# dac-layout.net
KiCad netlist of a schematic drawn in Altium Designer
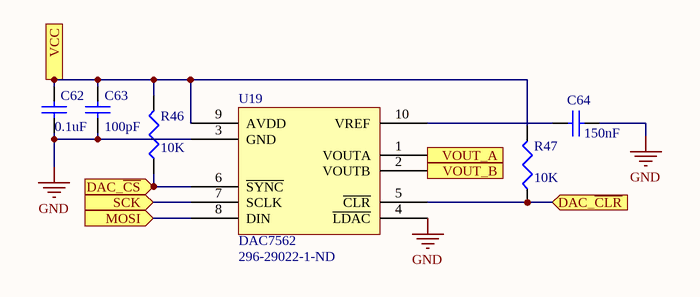
[diagram p0: dac-layout.SchDoc]

(export (version "E")
  (design (tool "Eeschema 10.0.6"))
  (components
    (comp (ref "C62")
      (value "0.1uF")
      (footprint "0402")
      (description "Capacitor (Semiconductor SIM Model)")
      (fields (field (name "PUBLISHER") "Altium Limited"))
      (libsource (lib "Miscellaneous Devices") (part "Cap Semi"))
    )
    (comp (ref "C63")
      (value "100pF")
      (footprint "0402")
      (description "Capacitor (Semiconductor SIM Model)")
      (fields (field (name "PUBLISHER") "Altium Limited"))
      (libsource (lib "Miscellaneous Devices") (part "Cap Semi"))
    )
    (comp (ref "C64")
      (value "150nF")
      (footprint "0402")
      (description "Capacitor (Semiconductor SIM Model)")
      (fields (field (name "PUBLISHER") "Altium Limited"))
      (libsource (lib "Miscellaneous Devices") (part "Cap Semi"))
    )
    (comp (ref "R46")
      (value "10K")
      (footprint "0402")
      (description "Resistor")
      (fields (field (name "PUBLISHER") "Altium Limited"))
      (libsource (lib "Miscellaneous Devices") (part "Res3"))
    )
    (comp (ref "R47")
      (value "10K")
      (footprint "0402")
      (description "Resistor")
      (fields (field (name "PUBLISHER") "Altium Limited"))
      (libsource (lib "Miscellaneous Devices") (part "Res3"))
    )
    (comp (ref "U19")
      (value "DAC7562")
      (footprint "SOP10-50P300X300-10N")
      (description "12-bit, low-power, voltage-output DAC with internal reference.")
      (fields (field (name "SUPPLIER PART NUMBER 1") "296-29022-1-ND"))
      (libsource (lib "PAY") (part "DAC7562"))
    )
  )
  (nets
    (net (code "1") (name "/DAC_~{CLR}") (class "Default")
      (node (ref "R47") (pin "1") (pinfunction "1_1") (pintype "passive"))
      (node (ref "U19") (pin "5") (pinfunction "~{CLR}_5") (pintype "passive"))
    )
    (net (code "2") (name "/DAC_~{CS}") (class "Default")
      (node (ref "R46") (pin "1") (pinfunction "1_1") (pintype "passive"))
      (node (ref "U19") (pin "6") (pinfunction "~{SYNC}_6") (pintype "passive"))
    )
    (net (code "3") (name "/MOSI") (class "Default")
      (node (ref "U19") (pin "8") (pinfunction "DIN_8") (pintype "passive"))
    )
    (net (code "4") (name "/SCK") (class "Default")
      (node (ref "U19") (pin "7") (pinfunction "SCLK_7") (pintype "passive"))
    )
    (net (code "5") (name "/VCC") (class "Default")
      (node (ref "C62") (pin "2") (pinfunction "2_2") (pintype "passive"))
      (node (ref "C63") (pin "2") (pinfunction "2_2") (pintype "passive"))
      (node (ref "R46") (pin "2") (pinfunction "2_2") (pintype "passive"))
      (node (ref "R47") (pin "2") (pinfunction "2_2") (pintype "passive"))
      (node (ref "U19") (pin "9") (pinfunction "AVDD_9") (pintype "passive"))
    )
    (net (code "6") (name "/VOUT_A") (class "Default")
      (node (ref "U19") (pin "1") (pinfunction "VOUTA_1") (pintype "passive"))
    )
    (net (code "7") (name "/VOUT_B") (class "Default")
      (node (ref "U19") (pin "2") (pinfunction "VOUTB_2") (pintype "passive"))
    )
    (net (code "8") (name "GND") (class "Default")
      (node (ref "C62") (pin "1") (pinfunction "1_1") (pintype "passive"))
      (node (ref "C63") (pin "1") (pinfunction "1_1") (pintype "passive"))
      (node (ref "C64") (pin "2") (pinfunction "2_2") (pintype "passive"))
      (node (ref "U19") (pin "3") (pinfunction "GND_3") (pintype "passive"))
      (node (ref "U19") (pin "4") (pinfunction "~{LDAC}_4") (pintype "passive"))
    )
    (net (code "9") (name "Net-(U19-VREF)") (class "Default")
      (node (ref "C64") (pin "1") (pinfunction "1_1") (pintype "passive"))
      (node (ref "U19") (pin "10") (pinfunction "VREF_10") (pintype "passive"))
    )
  )
)
